# RADIO.net
KiCad netlist of a schematic drawn in Altium Designer
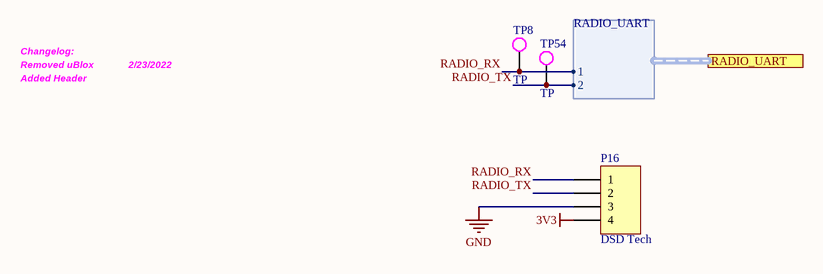
[diagram p0: RADIO.SchDoc]

(export (version "E")
  (design (tool "Eeschema 10.0.6"))
  (components
    (comp (ref "P16")
      (value "DSD Tech")
      (footprint "HDR1X4")
      (description "Header, 4-Pin")
      (fields (field (name "PUBLISHER") "Altium Limited"))
      (libsource (lib "Miscellaneous Connectors") (part "Header 4"))
    )
    (comp (ref "TP8")
      (value "TP")
      (footprint "Test_point")
      (description "Test Point")
      (libsource (lib "Arturo_Approved") (part "TP_PCB"))
    )
    (comp (ref "TP54")
      (value "TP")
      (footprint "Test_point")
      (description "Test Point")
      (libsource (lib "Arturo_Approved") (part "TP_PCB"))
    )
  )
  (nets
    (net (code "2") (name "/RADIO_RX") (class "Default")
      (node (ref "P16") (pin "1") (pinfunction "1_1") (pintype "passive"))
      (node (ref "TP8") (pin "1") (pinfunction "1_1") (pintype "passive"))
    )
    (net (code "3") (name "/RADIO_TX") (class "Default")
      (node (ref "P16") (pin "2") (pinfunction "2_2") (pintype "passive"))
      (node (ref "TP54") (pin "1") (pinfunction "1_1") (pintype "passive"))
    )
    (net (code "5") (name "3V3") (class "Default")
      (node (ref "P16") (pin "4") (pinfunction "4_4") (pintype "passive"))
    )
    (net (code "6") (name "GND") (class "Default")
      (node (ref "P16") (pin "3") (pinfunction "3_3") (pintype "passive"))
    )
  )
)
